# PRoyecto.net
KiCad netlist of a schematic drawn in EAGLE
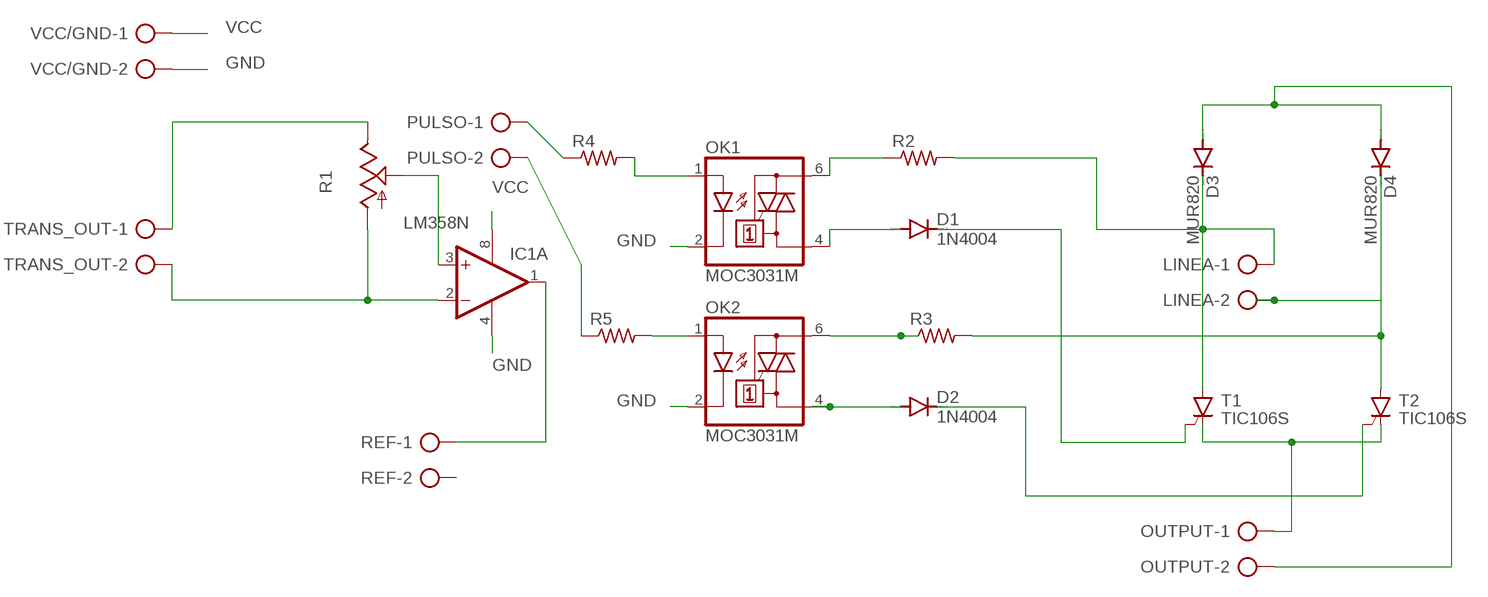
[diagram p0: schematic, sheet 1]

(export (version "E")
  (design (tool "Eeschema 10.0.6"))
  (components
    (comp (ref "D1")
      (value "1N4004")
      (footprint "eagle-import:DO41-10")
      (libsource (lib "eagle-import") (part "1N4004"))
    )
    (comp (ref "D2")
      (value "1N4004")
      (footprint "eagle-import:DO41-10")
      (libsource (lib "eagle-import") (part "1N4004"))
    )
    (comp (ref "D3")
      (value "MUR820")
      (footprint "eagle-import:C221B1A")
      (libsource (lib "eagle-import") (part "MUR820"))
    )
    (comp (ref "D4")
      (value "MUR820")
      (footprint "eagle-import:C221B1A")
      (libsource (lib "eagle-import") (part "MUR820"))
    )
    (comp (ref "IC1")
      (value "LM358N")
      (footprint "eagle-import:DIL08")
      (libsource (lib "eagle-import") (part "LM358N"))
    )
    (comp (ref "LINEA")
      (value "AK500/2-H")
      (footprint "eagle-import:AK500_2-H")
      (libsource (lib "eagle-import") (part "AK500/2-H"))
    )
    (comp (ref "OK1")
      (value "MOC3031M")
      (footprint "eagle-import:DIL06")
      (fields (field (name "MF") "FAIRCHILD SEMICONDUCTOR"))
      (libsource (lib "eagle-import") (part "MOC3031M"))
    )
    (comp (ref "OK2")
      (value "MOC3031M")
      (footprint "eagle-import:DIL06")
      (fields (field (name "MF") "FAIRCHILD SEMICONDUCTOR"))
      (libsource (lib "eagle-import") (part "MOC3031M"))
    )
    (comp (ref "OUTPUT")
      (value "AK500/2-H")
      (footprint "eagle-import:AK500_2-H")
      (libsource (lib "eagle-import") (part "AK500/2-H"))
    )
    (comp (ref "PULSO")
      (value "AK500/2-H")
      (footprint "eagle-import:AK500_2-H")
      (libsource (lib "eagle-import") (part "AK500/2-H"))
    )
    (comp (ref "R1")
      (value "TRIM_US-CIP20C-4MM")
      (footprint "eagle-import:CIP20C-4MM")
      (libsource (lib "eagle-import") (part "TRIM_US-CIP20C-4MM"))
    )
    (comp (ref "R2")
      (value "R-US_0207/12")
      (footprint "eagle-import:0207_12")
      (libsource (lib "eagle-import") (part "R-US_0207/12"))
    )
    (comp (ref "R3")
      (value "R-US_0207/12")
      (footprint "eagle-import:0207_12")
      (libsource (lib "eagle-import") (part "R-US_0207/12"))
    )
    (comp (ref "R4")
      (value "R-US_0207/12")
      (footprint "eagle-import:0207_12")
      (libsource (lib "eagle-import") (part "R-US_0207/12"))
    )
    (comp (ref "R5")
      (value "R-US_0207/12")
      (footprint "eagle-import:0207_12")
      (libsource (lib "eagle-import") (part "R-US_0207/12"))
    )
    (comp (ref "REF")
      (value "AK500/2-H")
      (footprint "eagle-import:AK500_2-H")
      (libsource (lib "eagle-import") (part "AK500/2-H"))
    )
    (comp (ref "T1")
      (value "TIC106S")
      (footprint "eagle-import:TIC106S")
      (libsource (lib "eagle-import") (part "TIC106S"))
    )
    (comp (ref "T2")
      (value "TIC106S")
      (footprint "eagle-import:TIC106S")
      (libsource (lib "eagle-import") (part "TIC106S"))
    )
    (comp (ref "TRANS_OUT")
      (value "AK500/2-H")
      (footprint "eagle-import:AK500_2-H")
      (libsource (lib "eagle-import") (part "AK500/2-H"))
    )
    (comp (ref "VCC/GND")
      (value "AK500/2-H")
      (footprint "eagle-import:AK500_2-H")
      (libsource (lib "eagle-import") (part "AK500/2-H"))
    )
  )
  (nets
    (net (code "1") (name "/GND") (class "Default")
      (node (ref "IC1") (pin "4") (pinfunction "V-_4") (pintype "power_in"))
      (node (ref "OK1") (pin "2") (pinfunction "C_2") (pintype "passive"))
      (node (ref "OK2") (pin "2") (pinfunction "C_2") (pintype "passive"))
      (node (ref "VCC/GND") (pin "2") (pinfunction "KL_2") (pintype "passive"))
    )
    (net (code "2") (name "/VCC") (class "Default")
      (node (ref "IC1") (pin "8") (pinfunction "V+_8") (pintype "power_in"))
      (node (ref "VCC/GND") (pin "1") (pinfunction "KL_1") (pintype "passive"))
    )
    (net (code "3") (name "Net-(D1-PadC)") (class "Default")
      (node (ref "D1") (pin "C") (pinfunction "C_C") (pintype "passive"))
      (node (ref "T1") (pin "G") (pinfunction "G_G") (pintype "passive"))
    )
    (net (code "4") (name "Net-(D2-PadC)") (class "Default")
      (node (ref "D2") (pin "C") (pinfunction "C_C") (pintype "passive"))
      (node (ref "T2") (pin "G") (pinfunction "G_G") (pintype "passive"))
    )
    (net (code "5") (name "Net-(IC1A-+IN)") (class "Default")
      (node (ref "IC1") (pin "3") (pinfunction "+IN_3") (pintype "input"))
      (node (ref "R1") (pin "S") (pinfunction "S_S") (pintype "passive"))
    )
    (net (code "6") (name "Net-(IC1A--IN)") (class "Default")
      (node (ref "IC1") (pin "2") (pinfunction "-IN_2") (pintype "input"))
      (node (ref "R1") (pin "A") (pinfunction "A_A") (pintype "passive"))
      (node (ref "TRANS_OUT") (pin "2") (pinfunction "KL_2") (pintype "passive"))
    )
    (net (code "7") (name "Net-(IC1A-OUT)") (class "Default")
      (node (ref "IC1") (pin "1") (pinfunction "OUT_1") (pintype "output"))
      (node (ref "REF") (pin "1") (pinfunction "KL_1") (pintype "passive"))
    )
    (net (code "8") (name "Net-(LINEAA-KL)") (class "Default")
      (node (ref "D3") (pin "C") (pinfunction "C_C") (pintype "passive"))
      (node (ref "LINEA") (pin "1") (pinfunction "KL_1") (pintype "passive"))
      (node (ref "R2") (pin "2") (pinfunction "2_2") (pintype "passive"))
      (node (ref "T1") (pin "A") (pinfunction "A_A") (pintype "passive"))
    )
    (net (code "9") (name "Net-(LINEAB-KL)") (class "Default")
      (node (ref "D4") (pin "C") (pinfunction "C_C") (pintype "passive"))
      (node (ref "LINEA") (pin "2") (pinfunction "KL_2") (pintype "passive"))
      (node (ref "R3") (pin "2") (pinfunction "2_2") (pintype "passive"))
      (node (ref "T2") (pin "A") (pinfunction "A_A") (pintype "passive"))
    )
    (net (code "10") (name "Net-(OK1-A)") (class "Default")
      (node (ref "OK1") (pin "1") (pinfunction "A_1") (pintype "passive"))
      (node (ref "R4") (pin "2") (pinfunction "2_2") (pintype "passive"))
    )
    (net (code "11") (name "Net-(OK1-A1)") (class "Default")
      (node (ref "D1") (pin "A") (pinfunction "A_A") (pintype "passive"))
      (node (ref "OK1") (pin "4") (pinfunction "A1_4") (pintype "passive"))
    )
    (net (code "12") (name "Net-(OK1-A2)") (class "Default")
      (node (ref "OK1") (pin "6") (pinfunction "A2_6") (pintype "passive"))
      (node (ref "R2") (pin "1") (pinfunction "1_1") (pintype "passive"))
    )
    (net (code "13") (name "Net-(OK2-A)") (class "Default")
      (node (ref "OK2") (pin "1") (pinfunction "A_1") (pintype "passive"))
      (node (ref "R5") (pin "2") (pinfunction "2_2") (pintype "passive"))
    )
    (net (code "14") (name "Net-(OK2-A1)") (class "Default")
      (node (ref "D2") (pin "A") (pinfunction "A_A") (pintype "passive"))
      (node (ref "OK2") (pin "4") (pinfunction "A1_4") (pintype "passive"))
    )
    (net (code "15") (name "Net-(OK2-A2)") (class "Default")
      (node (ref "OK2") (pin "6") (pinfunction "A2_6") (pintype "passive"))
      (node (ref "R3") (pin "1") (pinfunction "1_1") (pintype "passive"))
    )
    (net (code "16") (name "Net-(OUTPUTA-KL)") (class "Default")
      (node (ref "OUTPUT") (pin "1") (pinfunction "KL_1") (pintype "passive"))
      (node (ref "T1") (pin "C") (pinfunction "C_C") (pintype "passive"))
      (node (ref "T2") (pin "C") (pinfunction "C_C") (pintype "passive"))
    )
    (net (code "17") (name "Net-(OUTPUTB-KL)") (class "Default")
      (node (ref "D3") (pin "A") (pinfunction "A_A") (pintype "passive"))
      (node (ref "D4") (pin "A") (pinfunction "A_A") (pintype "passive"))
      (node (ref "OUTPUT") (pin "2") (pinfunction "KL_2") (pintype "passive"))
    )
    (net (code "18") (name "Net-(PULSOA-KL)") (class "Default")
      (node (ref "PULSO") (pin "1") (pinfunction "KL_1") (pintype "passive"))
      (node (ref "R4") (pin "1") (pinfunction "1_1") (pintype "passive"))
    )
    (net (code "19") (name "Net-(PULSOB-KL)") (class "Default")
      (node (ref "PULSO") (pin "2") (pinfunction "KL_2") (pintype "passive"))
      (node (ref "R5") (pin "1") (pinfunction "1_1") (pintype "passive"))
    )
    (net (code "20") (name "Net-(TRANS_OUTA-KL)") (class "Default")
      (node (ref "R1") (pin "E") (pinfunction "E_E") (pintype "passive"))
      (node (ref "TRANS_OUT") (pin "1") (pinfunction "KL_1") (pintype "passive"))
    )
    (net (code "21") (name "unconnected-(REFB-KL-Pad2)") (class "Default")
      (node (ref "REF") (pin "2") (pinfunction "KL_2") (pintype "passive"))
    )
  )
)
